# ttag.net
KiCad netlist of a schematic drawn in EAGLE
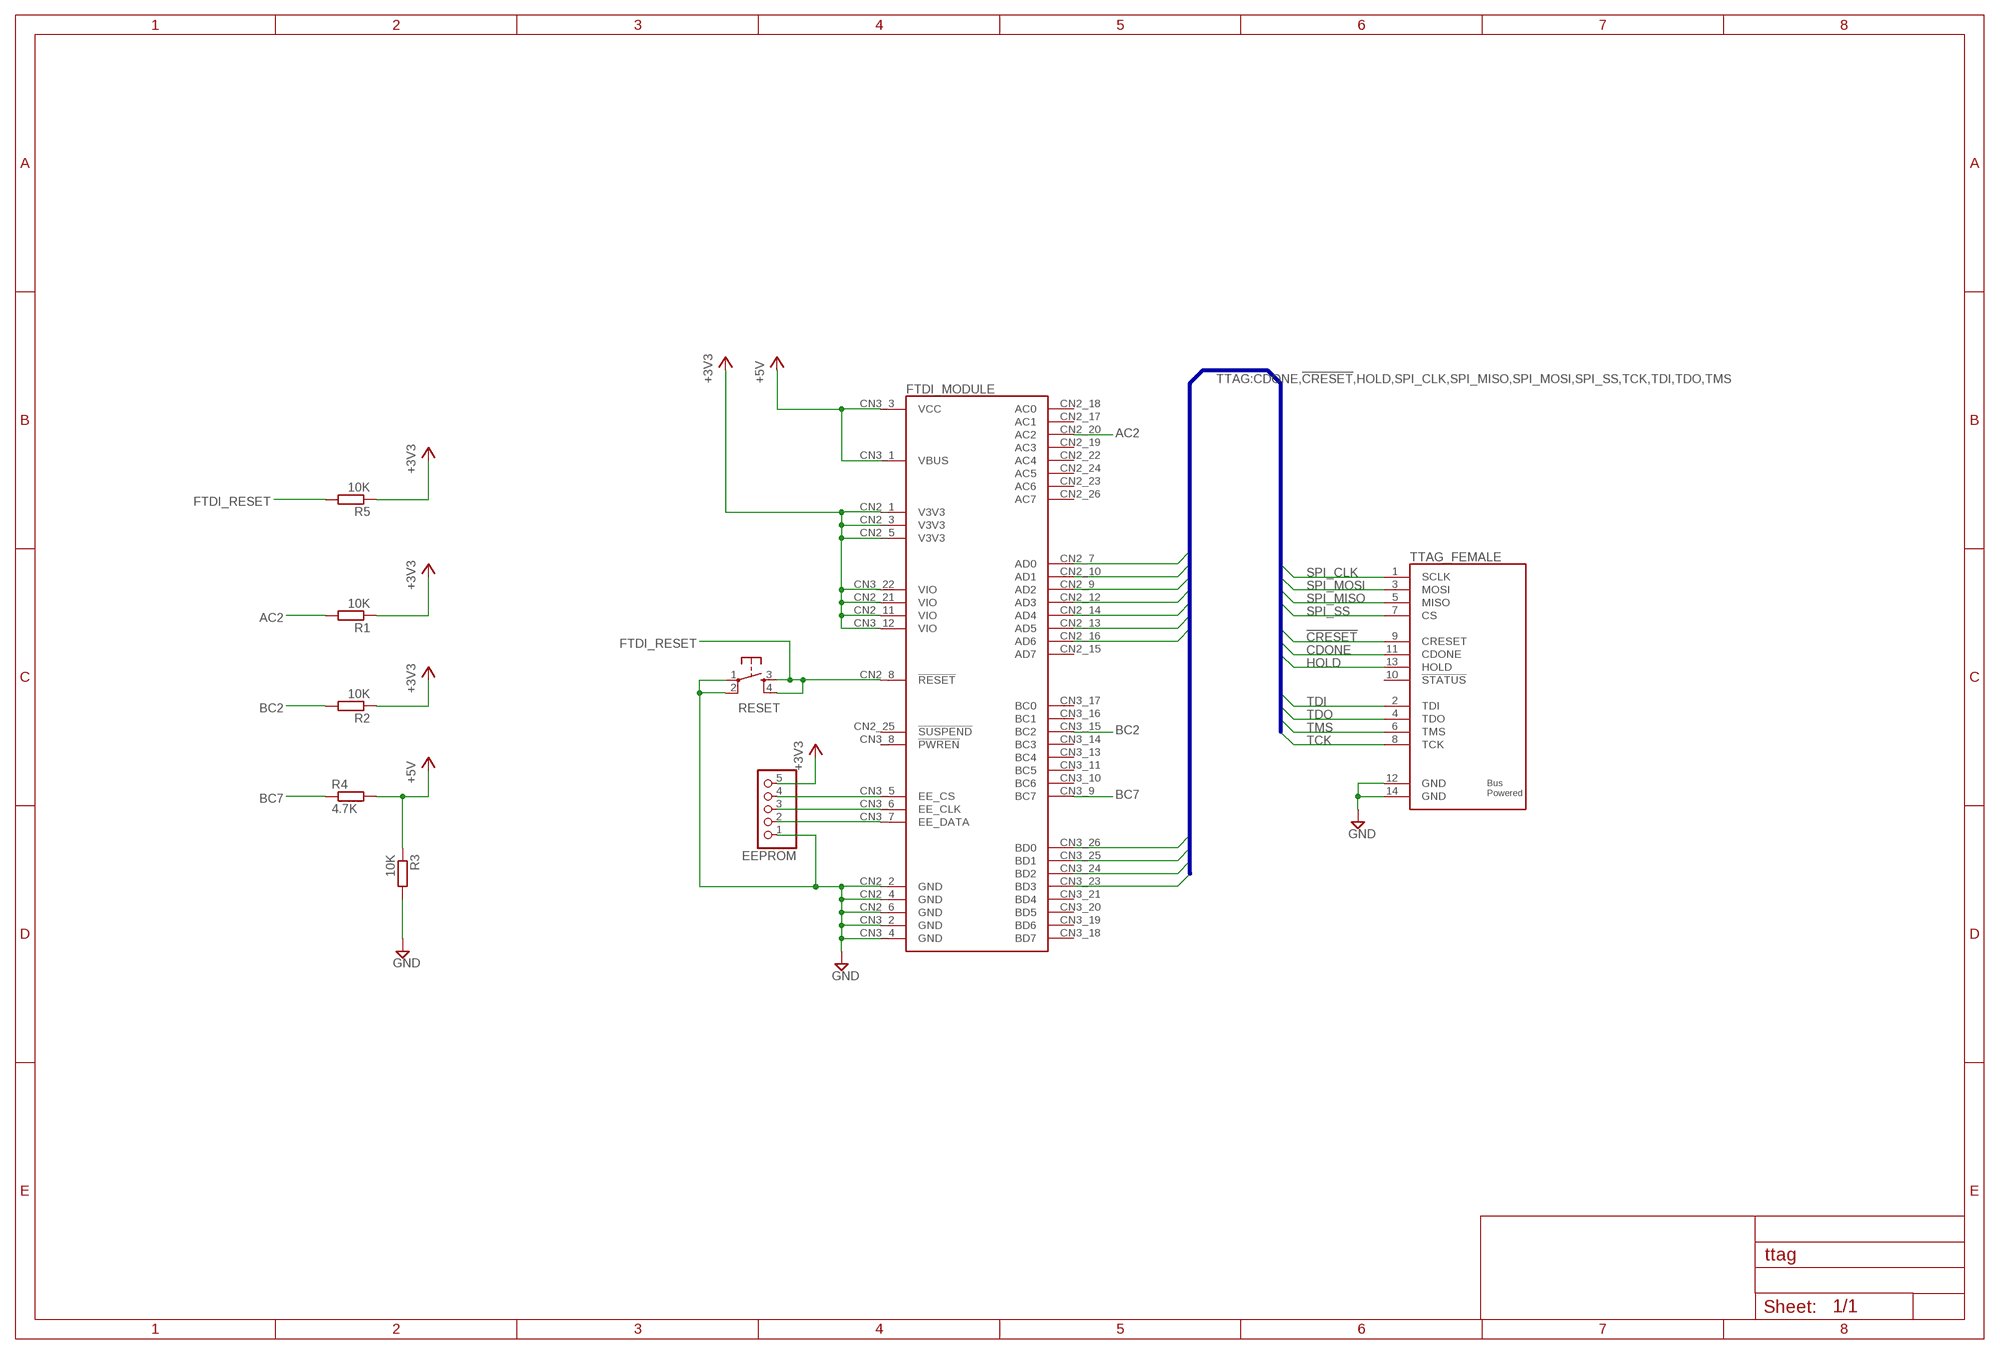
[diagram p0: schematic, sheet 1]

(export (version "E")
  (design (tool "Eeschema 10.0.6"))
  (components
    (comp (ref "EEPROM")
      (value "PINHD-1X05_2.54")
      (footprint "eagle-import:1X05")
      (libsource (lib "eagle-import") (part "PINHD-1X05_2.54"))
    )
    (comp (ref "FTDI_MODULE")
      (value "FTDI_MODULE")
      (footprint "eagle-import:FTDI_MODULE")
      (libsource (lib "eagle-import") (part "FTDI_MODULE"))
    )
    (comp (ref "R1")
      (value "10K")
      (footprint "eagle-import:M1206")
      (libsource (lib "eagle-import") (part "R-EU_M1206"))
    )
    (comp (ref "R2")
      (value "10K")
      (footprint "eagle-import:M1206")
      (libsource (lib "eagle-import") (part "R-EU_M1206"))
    )
    (comp (ref "R3")
      (value "10K")
      (footprint "eagle-import:M1206")
      (libsource (lib "eagle-import") (part "R-EU_M1206"))
    )
    (comp (ref "R4")
      (value "4.7K")
      (footprint "eagle-import:M1206")
      (libsource (lib "eagle-import") (part "R-EU_M1206"))
    )
    (comp (ref "R5")
      (value "10K")
      (footprint "eagle-import:M1206")
      (libsource (lib "eagle-import") (part "R-EU_M1206"))
    )
    (comp (ref "RESET")
      (value "TAC_SWITCHPTH")
      (footprint "eagle-import:TACTILE-PTH")
      (fields (field (name "DNF") "1") (field (name "USE") "B3F-1005"))
      (libsource (lib "eagle-import") (part "TAC_SWITCHPTH"))
    )
    (comp (ref "TTAG_FEMALE")
      (value "TTAG_F")
      (footprint "eagle-import:SFH11PBPCD07RABK")
      (fields (field (name "MANUFACTURER_PART_NUMBER") "SFH11-PBPC-D07-RA-BK"))
      (libsource (lib "eagle-import") (part "TTAG_F"))
    )
  )
  (nets
    (net (code "2") (name "+3V3") (class "Default")
      (node (ref "EEPROM") (pin "5") (pinfunction "5_5") (pintype "passive"))
      (node (ref "FTDI_MODULE") (pin "CN2_1") (pinfunction "V3V3_CN2_1") (pintype "bidirectional"))
      (node (ref "FTDI_MODULE") (pin "CN2_11") (pinfunction "VIO_CN2_11") (pintype "bidirectional"))
      (node (ref "FTDI_MODULE") (pin "CN2_21") (pinfunction "VIO_CN2_21") (pintype "bidirectional"))
      (node (ref "FTDI_MODULE") (pin "CN2_3") (pinfunction "V3V3_CN2_3") (pintype "bidirectional"))
      (node (ref "FTDI_MODULE") (pin "CN2_5") (pinfunction "V3V3_CN2_5") (pintype "bidirectional"))
      (node (ref "FTDI_MODULE") (pin "CN3_12") (pinfunction "VIO_CN3_12") (pintype "bidirectional"))
      (node (ref "FTDI_MODULE") (pin "CN3_22") (pinfunction "VIO_CN3_22") (pintype "bidirectional"))
      (node (ref "R1") (pin "1") (pinfunction "1_1") (pintype "passive"))
      (node (ref "R2") (pin "1") (pinfunction "1_1") (pintype "passive"))
      (node (ref "R5") (pin "1") (pinfunction "1_1") (pintype "passive"))
    )
    (net (code "3") (name "+5V") (class "Default")
      (node (ref "FTDI_MODULE") (pin "CN3_1") (pinfunction "VBUS_CN3_1") (pintype "bidirectional"))
      (node (ref "FTDI_MODULE") (pin "CN3_3") (pinfunction "VCC_CN3_3") (pintype "bidirectional"))
      (node (ref "R3") (pin "1") (pinfunction "1_1") (pintype "passive"))
      (node (ref "R4") (pin "2") (pinfunction "2_2") (pintype "passive"))
    )
    (net (code "4") (name "/AC2") (class "Default")
      (node (ref "FTDI_MODULE") (pin "CN2_20") (pinfunction "AC2_CN2_20") (pintype "bidirectional"))
      (node (ref "R1") (pin "2") (pinfunction "2_2") (pintype "passive"))
    )
    (net (code "5") (name "/BC2") (class "Default")
      (node (ref "FTDI_MODULE") (pin "CN3_15") (pinfunction "BC2_CN3_15") (pintype "bidirectional"))
      (node (ref "R2") (pin "2") (pinfunction "2_2") (pintype "passive"))
    )
    (net (code "6") (name "/BC7") (class "Default")
      (node (ref "FTDI_MODULE") (pin "CN3_9") (pinfunction "BC7_CN3_9") (pintype "bidirectional"))
      (node (ref "R4") (pin "1") (pinfunction "1_1") (pintype "passive"))
    )
    (net (code "7") (name "/CDONE") (class "Default")
      (node (ref "FTDI_MODULE") (pin "CN2_13") (pinfunction "AD5_CN2_13") (pintype "bidirectional"))
      (node (ref "TTAG_FEMALE") (pin "11") (pinfunction "CDONE_11") (pintype "bidirectional"))
    )
    (net (code "8") (name "/FTDI_RESET") (class "Default")
      (node (ref "FTDI_MODULE") (pin "CN2_8") (pinfunction "~{RESET}_CN2_8") (pintype "bidirectional"))
      (node (ref "R5") (pin "2") (pinfunction "2_2") (pintype "passive"))
      (node (ref "RESET") (pin "3") (pinfunction "3_3") (pintype "passive"))
      (node (ref "RESET") (pin "4") (pinfunction "4_4") (pintype "passive"))
    )
    (net (code "9") (name "/HOLD") (class "Default")
      (node (ref "FTDI_MODULE") (pin "CN2_16") (pinfunction "AD6_CN2_16") (pintype "bidirectional"))
      (node (ref "TTAG_FEMALE") (pin "13") (pinfunction "HOLD_13") (pintype "bidirectional"))
    )
    (net (code "10") (name "/SPI_CLK") (class "Default")
      (node (ref "FTDI_MODULE") (pin "CN2_7") (pinfunction "AD0_CN2_7") (pintype "bidirectional"))
      (node (ref "TTAG_FEMALE") (pin "1") (pinfunction "SCLK_1") (pintype "bidirectional"))
    )
    (net (code "11") (name "/SPI_MISO") (class "Default")
      (node (ref "FTDI_MODULE") (pin "CN2_9") (pinfunction "AD2_CN2_9") (pintype "bidirectional"))
      (node (ref "TTAG_FEMALE") (pin "5") (pinfunction "MISO_5") (pintype "bidirectional"))
    )
    (net (code "12") (name "/SPI_MOSI") (class "Default")
      (node (ref "FTDI_MODULE") (pin "CN2_10") (pinfunction "AD1_CN2_10") (pintype "bidirectional"))
      (node (ref "TTAG_FEMALE") (pin "3") (pinfunction "MOSI_3") (pintype "bidirectional"))
    )
    (net (code "13") (name "/SPI_SS") (class "Default")
      (node (ref "FTDI_MODULE") (pin "CN2_12") (pinfunction "AD3_CN2_12") (pintype "bidirectional"))
      (node (ref "TTAG_FEMALE") (pin "7") (pinfunction "CS_7") (pintype "bidirectional"))
    )
    (net (code "14") (name "/TCK") (class "Default")
      (node (ref "FTDI_MODULE") (pin "CN3_26") (pinfunction "BD0_CN3_26") (pintype "bidirectional"))
      (node (ref "TTAG_FEMALE") (pin "8") (pinfunction "TCK_8") (pintype "bidirectional"))
    )
    (net (code "15") (name "/TDI") (class "Default")
      (node (ref "FTDI_MODULE") (pin "CN3_25") (pinfunction "BD1_CN3_25") (pintype "bidirectional"))
      (node (ref "TTAG_FEMALE") (pin "2") (pinfunction "TDI_2") (pintype "bidirectional"))
    )
    (net (code "16") (name "/TDO") (class "Default")
      (node (ref "FTDI_MODULE") (pin "CN3_24") (pinfunction "BD2_CN3_24") (pintype "bidirectional"))
      (node (ref "TTAG_FEMALE") (pin "4") (pinfunction "TDO_4") (pintype "bidirectional"))
    )
    (net (code "17") (name "/TMS") (class "Default")
      (node (ref "FTDI_MODULE") (pin "CN3_23") (pinfunction "BD3_CN3_23") (pintype "bidirectional"))
      (node (ref "TTAG_FEMALE") (pin "6") (pinfunction "TMS_6") (pintype "bidirectional"))
    )
    (net (code "19") (name "/~{CRESET}") (class "Default")
      (node (ref "FTDI_MODULE") (pin "CN2_14") (pinfunction "AD4_CN2_14") (pintype "bidirectional"))
      (node (ref "TTAG_FEMALE") (pin "9") (pinfunction "CRESET_9") (pintype "bidirectional"))
    )
    (net (code "20") (name "GND") (class "Default")
      (node (ref "EEPROM") (pin "1") (pinfunction "1_1") (pintype "passive"))
      (node (ref "FTDI_MODULE") (pin "CN2_2") (pinfunction "GND_CN2_2") (pintype "bidirectional"))
      (node (ref "FTDI_MODULE") (pin "CN2_4") (pinfunction "GND_CN2_4") (pintype "bidirectional"))
      (node (ref "FTDI_MODULE") (pin "CN2_6") (pinfunction "GND_CN2_6") (pintype "bidirectional"))
      (node (ref "FTDI_MODULE") (pin "CN3_2") (pinfunction "GND_CN3_2") (pintype "bidirectional"))
      (node (ref "FTDI_MODULE") (pin "CN3_4") (pinfunction "GND_CN3_4") (pintype "bidirectional"))
      (node (ref "R3") (pin "2") (pinfunction "2_2") (pintype "passive"))
      (node (ref "RESET") (pin "1") (pinfunction "1_1") (pintype "passive"))
      (node (ref "RESET") (pin "2") (pinfunction "2_2") (pintype "passive"))
      (node (ref "TTAG_FEMALE") (pin "12") (pinfunction "GND_12") (pintype "bidirectional"))
      (node (ref "TTAG_FEMALE") (pin "14") (pinfunction "GND_14") (pintype "bidirectional"))
    )
    (net (code "21") (name "Net-(FTDI_MODULE-EE_CLK)") (class "Default")
      (node (ref "EEPROM") (pin "3") (pinfunction "3_3") (pintype "passive"))
      (node (ref "FTDI_MODULE") (pin "CN3_6") (pinfunction "EE_CLK_CN3_6") (pintype "bidirectional"))
    )
    (net (code "22") (name "Net-(FTDI_MODULE-EE_CS)") (class "Default")
      (node (ref "EEPROM") (pin "4") (pinfunction "4_4") (pintype "passive"))
      (node (ref "FTDI_MODULE") (pin "CN3_5") (pinfunction "EE_CS_CN3_5") (pintype "bidirectional"))
    )
    (net (code "23") (name "Net-(FTDI_MODULE-EE_DATA)") (class "Default")
      (node (ref "EEPROM") (pin "2") (pinfunction "2_2") (pintype "passive"))
      (node (ref "FTDI_MODULE") (pin "CN3_7") (pinfunction "EE_DATA_CN3_7") (pintype "bidirectional"))
    )
    (net (code "24") (name "unconnected-(FTDI_MODULE-AC0-PadCN2_18)") (class "Default")
      (node (ref "FTDI_MODULE") (pin "CN2_18") (pinfunction "AC0_CN2_18") (pintype "bidirectional"))
    )
    (net (code "25") (name "unconnected-(FTDI_MODULE-AC1-PadCN2_17)") (class "Default")
      (node (ref "FTDI_MODULE") (pin "CN2_17") (pinfunction "AC1_CN2_17") (pintype "bidirectional"))
    )
    (net (code "26") (name "unconnected-(FTDI_MODULE-AC3-PadCN2_19)") (class "Default")
      (node (ref "FTDI_MODULE") (pin "CN2_19") (pinfunction "AC3_CN2_19") (pintype "bidirectional"))
    )
    (net (code "27") (name "unconnected-(FTDI_MODULE-AC4-PadCN2_22)") (class "Default")
      (node (ref "FTDI_MODULE") (pin "CN2_22") (pinfunction "AC4_CN2_22") (pintype "bidirectional"))
    )
    (net (code "28") (name "unconnected-(FTDI_MODULE-AC5-PadCN2_24)") (class "Default")
      (node (ref "FTDI_MODULE") (pin "CN2_24") (pinfunction "AC5_CN2_24") (pintype "bidirectional"))
    )
    (net (code "29") (name "unconnected-(FTDI_MODULE-AC6-PadCN2_23)") (class "Default")
      (node (ref "FTDI_MODULE") (pin "CN2_23") (pinfunction "AC6_CN2_23") (pintype "bidirectional"))
    )
    (net (code "30") (name "unconnected-(FTDI_MODULE-AC7-PadCN2_26)") (class "Default")
      (node (ref "FTDI_MODULE") (pin "CN2_26") (pinfunction "AC7_CN2_26") (pintype "bidirectional"))
    )
    (net (code "31") (name "unconnected-(FTDI_MODULE-AD7-PadCN2_15)") (class "Default")
      (node (ref "FTDI_MODULE") (pin "CN2_15") (pinfunction "AD7_CN2_15") (pintype "bidirectional"))
    )
    (net (code "32") (name "unconnected-(FTDI_MODULE-BC0-PadCN3_17)") (class "Default")
      (node (ref "FTDI_MODULE") (pin "CN3_17") (pinfunction "BC0_CN3_17") (pintype "bidirectional"))
    )
    (net (code "33") (name "unconnected-(FTDI_MODULE-BC1-PadCN3_16)") (class "Default")
      (node (ref "FTDI_MODULE") (pin "CN3_16") (pinfunction "BC1_CN3_16") (pintype "bidirectional"))
    )
    (net (code "34") (name "unconnected-(FTDI_MODULE-BC3-PadCN3_14)") (class "Default")
      (node (ref "FTDI_MODULE") (pin "CN3_14") (pinfunction "BC3_CN3_14") (pintype "bidirectional"))
    )
    (net (code "35") (name "unconnected-(FTDI_MODULE-BC4-PadCN3_13)") (class "Default")
      (node (ref "FTDI_MODULE") (pin "CN3_13") (pinfunction "BC4_CN3_13") (pintype "bidirectional"))
    )
    (net (code "36") (name "unconnected-(FTDI_MODULE-BC5-PadCN3_11)") (class "Default")
      (node (ref "FTDI_MODULE") (pin "CN3_11") (pinfunction "BC5_CN3_11") (pintype "bidirectional"))
    )
    (net (code "37") (name "unconnected-(FTDI_MODULE-BC6-PadCN3_10)") (class "Default")
      (node (ref "FTDI_MODULE") (pin "CN3_10") (pinfunction "BC6_CN3_10") (pintype "bidirectional"))
    )
    (net (code "38") (name "unconnected-(FTDI_MODULE-BD4-PadCN3_21)") (class "Default")
      (node (ref "FTDI_MODULE") (pin "CN3_21") (pinfunction "BD4_CN3_21") (pintype "bidirectional"))
    )
    (net (code "39") (name "unconnected-(FTDI_MODULE-BD5-PadCN3_20)") (class "Default")
      (node (ref "FTDI_MODULE") (pin "CN3_20") (pinfunction "BD5_CN3_20") (pintype "bidirectional"))
    )
    (net (code "40") (name "unconnected-(FTDI_MODULE-BD6-PadCN3_19)") (class "Default")
      (node (ref "FTDI_MODULE") (pin "CN3_19") (pinfunction "BD6_CN3_19") (pintype "bidirectional"))
    )
    (net (code "41") (name "unconnected-(FTDI_MODULE-BD7-PadCN3_18)") (class "Default")
      (node (ref "FTDI_MODULE") (pin "CN3_18") (pinfunction "BD7_CN3_18") (pintype "bidirectional"))
    )
    (net (code "42") (name "unconnected-(FTDI_MODULE-~{PWREN}-PadCN3_8)") (class "Default")
      (node (ref "FTDI_MODULE") (pin "CN3_8") (pinfunction "~{PWREN}_CN3_8") (pintype "bidirectional"))
    )
    (net (code "43") (name "unconnected-(FTDI_MODULE-~{SUSPEND}-PadCN2_25)") (class "Default")
      (node (ref "FTDI_MODULE") (pin "CN2_25") (pinfunction "~{SUSPEND}_CN2_25") (pintype "bidirectional"))
    )
    (net (code "44") (name "unconnected-(TTAG_FEMALE-~{STATUS}-Pad10)") (class "Default")
      (node (ref "TTAG_FEMALE") (pin "10") (pinfunction "~{STATUS}_10") (pintype "bidirectional"))
    )
  )
)
